# fpga13-serdes-power.net
KiCad netlist of a schematic drawn in Altium Designer
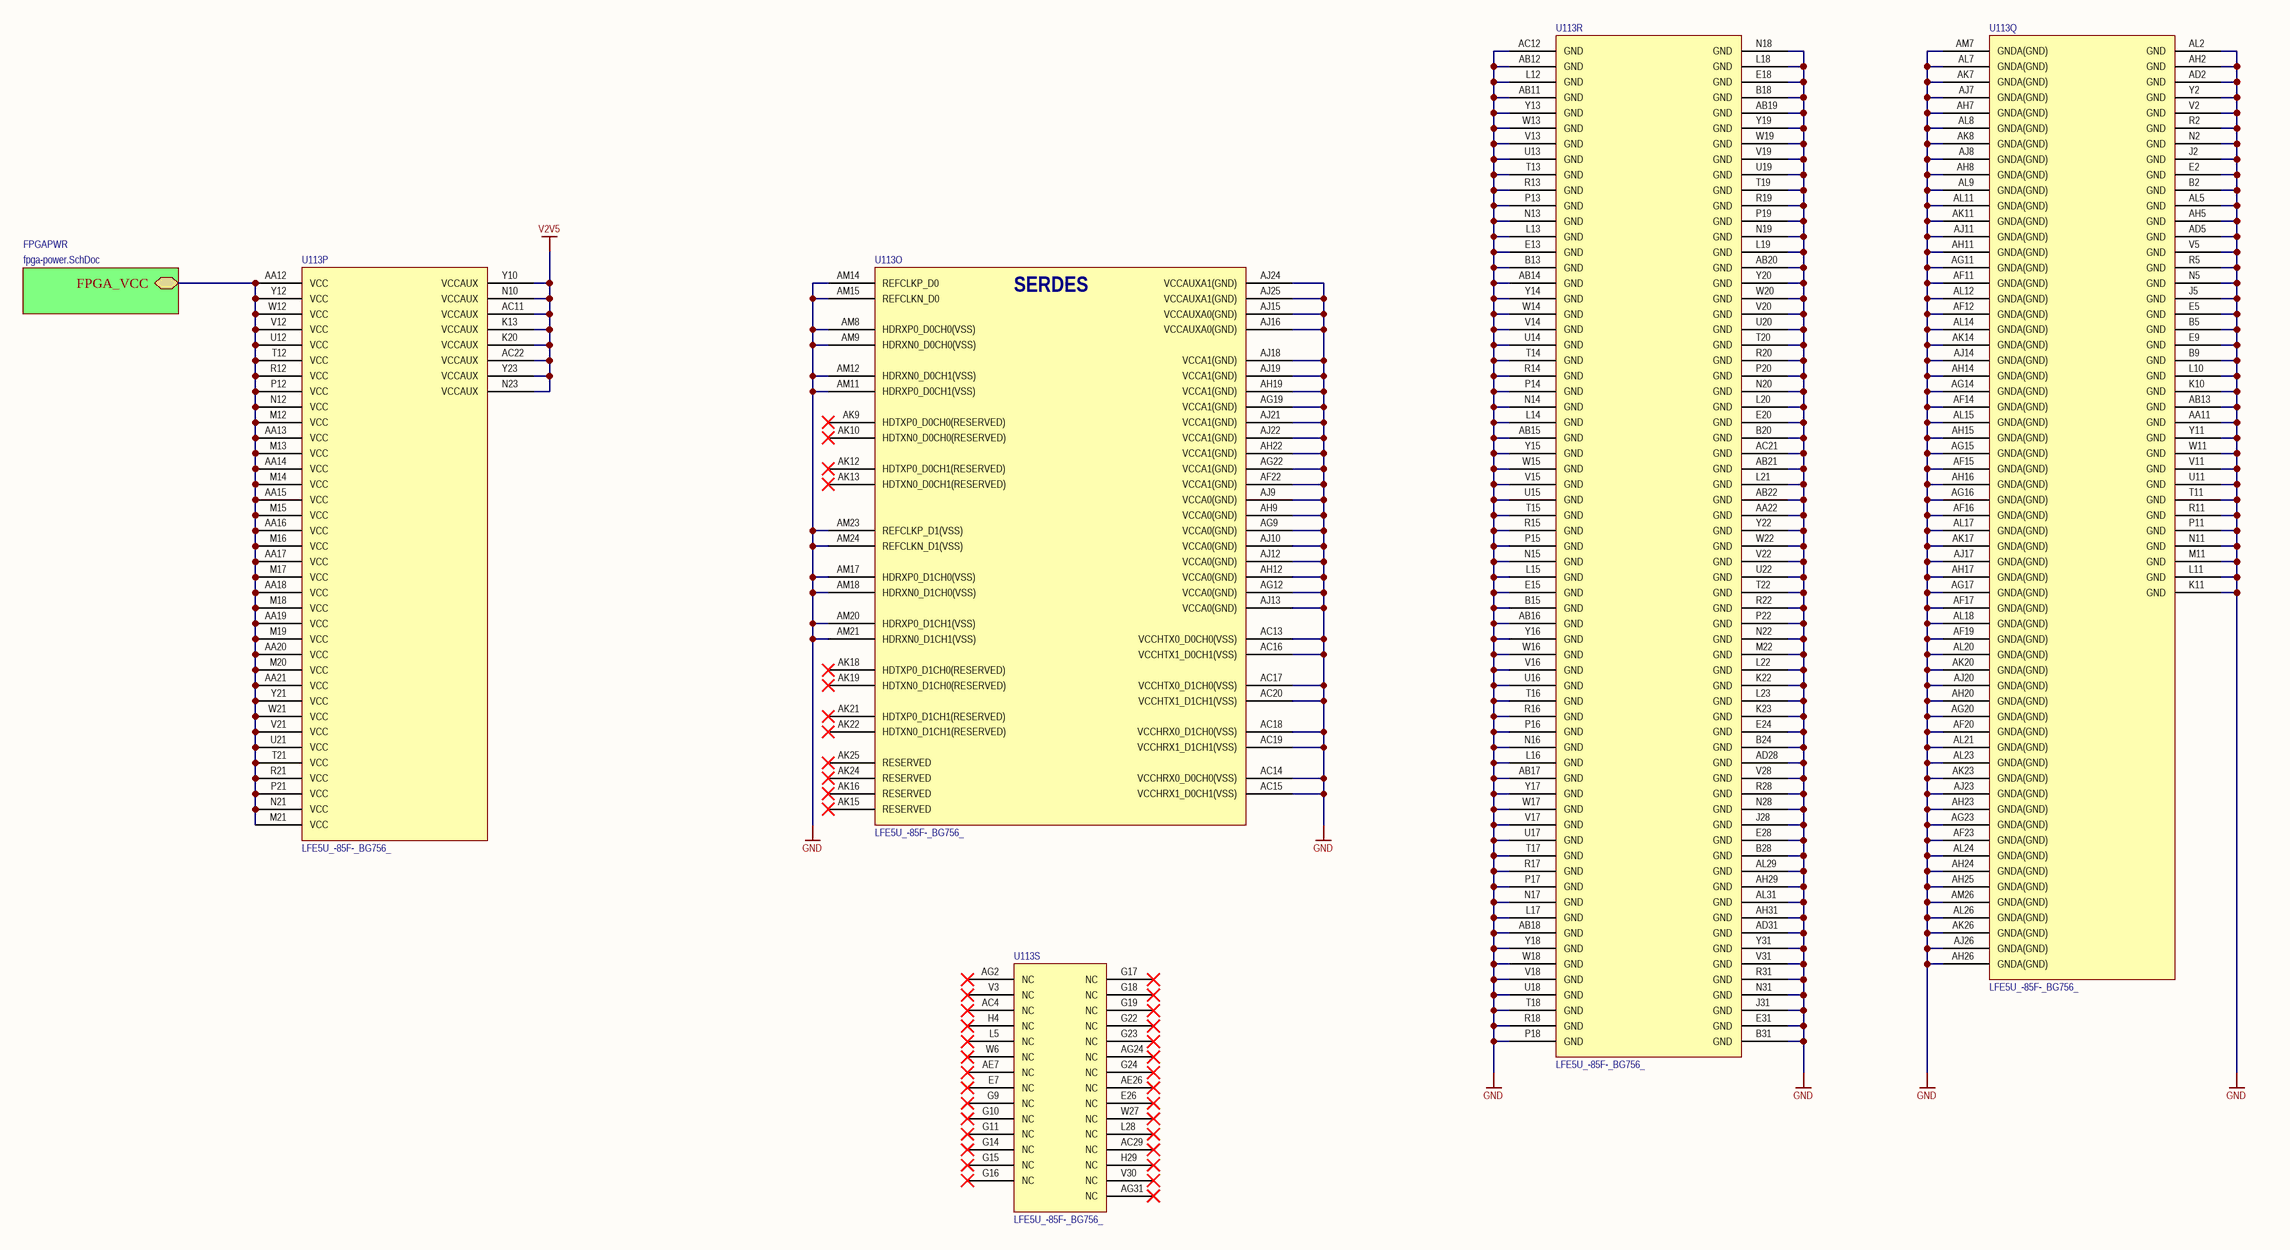
[diagram p0: fpga13-serdes-power.SchDoc]

(export (version "E")
  (design (tool "Eeschema 10.0.6"))
  (components
    (comp (ref "U113")
      (value "LFE5U_-85F-_BG756_")
      (footprint "lattice:caBGA756")
      (description "ECP5 FPGA, 85k LUT, 756-caBGA")
      (fields (field (name "MANUFACTURER") "Lattice Semiconductor"))
      (libsource (lib "lattice") (part "LFE5U_-85F-_BG756_"))
    )
  )
  (nets
    (net (code "1") (name "/FPGA_VCC") (class "Default")
      (node (ref "U113") (pin "AA12") (pinfunction "VCC_AA12") (pintype "power_in"))
      (node (ref "U113") (pin "AA13") (pinfunction "VCC_AA13") (pintype "power_in"))
      (node (ref "U113") (pin "AA14") (pinfunction "VCC_AA14") (pintype "power_in"))
      (node (ref "U113") (pin "AA15") (pinfunction "VCC_AA15") (pintype "power_in"))
      (node (ref "U113") (pin "AA16") (pinfunction "VCC_AA16") (pintype "power_in"))
      (node (ref "U113") (pin "AA17") (pinfunction "VCC_AA17") (pintype "power_in"))
      (node (ref "U113") (pin "AA18") (pinfunction "VCC_AA18") (pintype "power_in"))
      (node (ref "U113") (pin "AA19") (pinfunction "VCC_AA19") (pintype "power_in"))
      (node (ref "U113") (pin "AA20") (pinfunction "VCC_AA20") (pintype "power_in"))
      (node (ref "U113") (pin "AA21") (pinfunction "VCC_AA21") (pintype "power_in"))
      (node (ref "U113") (pin "M12") (pinfunction "VCC_M12") (pintype "power_in"))
      (node (ref "U113") (pin "M13") (pinfunction "VCC_M13") (pintype "power_in"))
      (node (ref "U113") (pin "M14") (pinfunction "VCC_M14") (pintype "power_in"))
      (node (ref "U113") (pin "M15") (pinfunction "VCC_M15") (pintype "power_in"))
      (node (ref "U113") (pin "M16") (pinfunction "VCC_M16") (pintype "power_in"))
      (node (ref "U113") (pin "M17") (pinfunction "VCC_M17") (pintype "power_in"))
      (node (ref "U113") (pin "M18") (pinfunction "VCC_M18") (pintype "power_in"))
      (node (ref "U113") (pin "M19") (pinfunction "VCC_M19") (pintype "power_in"))
      (node (ref "U113") (pin "M20") (pinfunction "VCC_M20") (pintype "power_in"))
      (node (ref "U113") (pin "M21") (pinfunction "VCC_M21") (pintype "power_in"))
      (node (ref "U113") (pin "N12") (pinfunction "VCC_N12") (pintype "power_in"))
      (node (ref "U113") (pin "N21") (pinfunction "VCC_N21") (pintype "power_in"))
      (node (ref "U113") (pin "P12") (pinfunction "VCC_P12") (pintype "power_in"))
      (node (ref "U113") (pin "P21") (pinfunction "VCC_P21") (pintype "power_in"))
      (node (ref "U113") (pin "R12") (pinfunction "VCC_R12") (pintype "power_in"))
      (node (ref "U113") (pin "R21") (pinfunction "VCC_R21") (pintype "power_in"))
      (node (ref "U113") (pin "T12") (pinfunction "VCC_T12") (pintype "power_in"))
      (node (ref "U113") (pin "T21") (pinfunction "VCC_T21") (pintype "power_in"))
      (node (ref "U113") (pin "U12") (pinfunction "VCC_U12") (pintype "power_in"))
      (node (ref "U113") (pin "U21") (pinfunction "VCC_U21") (pintype "power_in"))
      (node (ref "U113") (pin "V12") (pinfunction "VCC_V12") (pintype "power_in"))
      (node (ref "U113") (pin "V21") (pinfunction "VCC_V21") (pintype "power_in"))
      (node (ref "U113") (pin "W12") (pinfunction "VCC_W12") (pintype "power_in"))
      (node (ref "U113") (pin "W21") (pinfunction "VCC_W21") (pintype "power_in"))
      (node (ref "U113") (pin "Y12") (pinfunction "VCC_Y12") (pintype "power_in"))
      (node (ref "U113") (pin "Y21") (pinfunction "VCC_Y21") (pintype "power_in"))
    )
    (net (code "2") (name "GND") (class "Default")
      (node (ref "U113") (pin "AA11") (pinfunction "GND_AA11") (pintype "power_in"))
      (node (ref "U113") (pin "AA22") (pinfunction "GND_AA22") (pintype "power_in"))
      (node (ref "U113") (pin "AB11") (pinfunction "GND_AB11") (pintype "power_in"))
      (node (ref "U113") (pin "AB12") (pinfunction "GND_AB12") (pintype "power_in"))
      (node (ref "U113") (pin "AB13") (pinfunction "GND_AB13") (pintype "power_in"))
      (node (ref "U113") (pin "AB14") (pinfunction "GND_AB14") (pintype "power_in"))
      (node (ref "U113") (pin "AB15") (pinfunction "GND_AB15") (pintype "power_in"))
      (node (ref "U113") (pin "AB16") (pinfunction "GND_AB16") (pintype "power_in"))
      (node (ref "U113") (pin "AB17") (pinfunction "GND_AB17") (pintype "power_in"))
      (node (ref "U113") (pin "AB18") (pinfunction "GND_AB18") (pintype "power_in"))
      (node (ref "U113") (pin "AB19") (pinfunction "GND_AB19") (pintype "power_in"))
      (node (ref "U113") (pin "AB20") (pinfunction "GND_AB20") (pintype "power_in"))
      (node (ref "U113") (pin "AB21") (pinfunction "GND_AB21") (pintype "power_in"))
      (node (ref "U113") (pin "AB22") (pinfunction "GND_AB22") (pintype "power_in"))
      (node (ref "U113") (pin "AC12") (pinfunction "GND_AC12") (pintype "power_in"))
      (node (ref "U113") (pin "AC13") (pinfunction "VCCHTX0_D0CH0(VSS)_AC13") (pintype "power_in"))
      (node (ref "U113") (pin "AC14") (pinfunction "VCCHRX0_D0CH0(VSS)_AC14") (pintype "power_in"))
      (node (ref "U113") (pin "AC15") (pinfunction "VCCHRX1_D0CH1(VSS)_AC15") (pintype "power_in"))
      (node (ref "U113") (pin "AC16") (pinfunction "VCCHTX1_D0CH1(VSS)_AC16") (pintype "power_in"))
      (node (ref "U113") (pin "AC17") (pinfunction "VCCHTX0_D1CH0(VSS)_AC17") (pintype "power_in"))
      (node (ref "U113") (pin "AC18") (pinfunction "VCCHRX0_D1CH0(VSS)_AC18") (pintype "power_in"))
      (node (ref "U113") (pin "AC19") (pinfunction "VCCHRX1_D1CH1(VSS)_AC19") (pintype "power_in"))
      (node (ref "U113") (pin "AC20") (pinfunction "VCCHTX1_D1CH1(VSS)_AC20") (pintype "power_in"))
      (node (ref "U113") (pin "AC21") (pinfunction "GND_AC21") (pintype "power_in"))
      (node (ref "U113") (pin "AD2") (pinfunction "GND_AD2") (pintype "power_in"))
      (node (ref "U113") (pin "AD28") (pinfunction "GND_AD28") (pintype "power_in"))
      (node (ref "U113") (pin "AD31") (pinfunction "GND_AD31") (pintype "power_in"))
      (node (ref "U113") (pin "AD5") (pinfunction "GND_AD5") (pintype "power_in"))
      (node (ref "U113") (pin "AF11") (pinfunction "GNDA(GND)_AF11") (pintype "power_in"))
      (node (ref "U113") (pin "AF12") (pinfunction "GNDA(GND)_AF12") (pintype "power_in"))
      (node (ref "U113") (pin "AF14") (pinfunction "GNDA(GND)_AF14") (pintype "power_in"))
      (node (ref "U113") (pin "AF15") (pinfunction "GNDA(GND)_AF15") (pintype "power_in"))
      (node (ref "U113") (pin "AF16") (pinfunction "GNDA(GND)_AF16") (pintype "power_in"))
      (node (ref "U113") (pin "AF17") (pinfunction "GNDA(GND)_AF17") (pintype "power_in"))
      (node (ref "U113") (pin "AF19") (pinfunction "GNDA(GND)_AF19") (pintype "power_in"))
      (node (ref "U113") (pin "AF20") (pinfunction "GNDA(GND)_AF20") (pintype "power_in"))
      (node (ref "U113") (pin "AF22") (pinfunction "VCCA1(GND)_AF22") (pintype "power_in"))
      (node (ref "U113") (pin "AF23") (pinfunction "GNDA(GND)_AF23") (pintype "power_in"))
      (node (ref "U113") (pin "AG11") (pinfunction "GNDA(GND)_AG11") (pintype "power_in"))
      (node (ref "U113") (pin "AG12") (pinfunction "VCCA0(GND)_AG12") (pintype "power_in"))
      (node (ref "U113") (pin "AG14") (pinfunction "GNDA(GND)_AG14") (pintype "power_in"))
      (node (ref "U113") (pin "AG15") (pinfunction "GNDA(GND)_AG15") (pintype "power_in"))
      (node (ref "U113") (pin "AG16") (pinfunction "GNDA(GND)_AG16") (pintype "power_in"))
      (node (ref "U113") (pin "AG17") (pinfunction "GNDA(GND)_AG17") (pintype "power_in"))
      (node (ref "U113") (pin "AG19") (pinfunction "VCCA1(GND)_AG19") (pintype "power_in"))
      (node (ref "U113") (pin "AG20") (pinfunction "GNDA(GND)_AG20") (pintype "power_in"))
      (node (ref "U113") (pin "AG22") (pinfunction "VCCA1(GND)_AG22") (pintype "power_in"))
      (node (ref "U113") (pin "AG23") (pinfunction "GNDA(GND)_AG23") (pintype "power_in"))
      (node (ref "U113") (pin "AG9") (pinfunction "VCCA0(GND)_AG9") (pintype "power_in"))
      (node (ref "U113") (pin "AH11") (pinfunction "GNDA(GND)_AH11") (pintype "power_in"))
      (node (ref "U113") (pin "AH12") (pinfunction "VCCA0(GND)_AH12") (pintype "power_in"))
      (node (ref "U113") (pin "AH14") (pinfunction "GNDA(GND)_AH14") (pintype "power_in"))
      (node (ref "U113") (pin "AH15") (pinfunction "GNDA(GND)_AH15") (pintype "power_in"))
      (node (ref "U113") (pin "AH16") (pinfunction "GNDA(GND)_AH16") (pintype "power_in"))
      (node (ref "U113") (pin "AH17") (pinfunction "GNDA(GND)_AH17") (pintype "power_in"))
      (node (ref "U113") (pin "AH19") (pinfunction "VCCA1(GND)_AH19") (pintype "power_in"))
      (node (ref "U113") (pin "AH2") (pinfunction "GND_AH2") (pintype "power_in"))
      (node (ref "U113") (pin "AH20") (pinfunction "GNDA(GND)_AH20") (pintype "power_in"))
      (node (ref "U113") (pin "AH22") (pinfunction "VCCA1(GND)_AH22") (pintype "power_in"))
      (node (ref "U113") (pin "AH23") (pinfunction "GNDA(GND)_AH23") (pintype "power_in"))
      (node (ref "U113") (pin "AH24") (pinfunction "GNDA(GND)_AH24") (pintype "power_in"))
      (node (ref "U113") (pin "AH25") (pinfunction "GNDA(GND)_AH25") (pintype "power_in"))
      (node (ref "U113") (pin "AH26") (pinfunction "GNDA(GND)_AH26") (pintype "power_in"))
      (node (ref "U113") (pin "AH29") (pinfunction "GND_AH29") (pintype "power_in"))
      (node (ref "U113") (pin "AH31") (pinfunction "GND_AH31") (pintype "power_in"))
      (node (ref "U113") (pin "AH5") (pinfunction "GND_AH5") (pintype "power_in"))
      (node (ref "U113") (pin "AH7") (pinfunction "GNDA(GND)_AH7") (pintype "power_in"))
      (node (ref "U113") (pin "AH8") (pinfunction "GNDA(GND)_AH8") (pintype "power_in"))
      (node (ref "U113") (pin "AH9") (pinfunction "VCCA0(GND)_AH9") (pintype "power_in"))
      (node (ref "U113") (pin "AJ10") (pinfunction "VCCA0(GND)_AJ10") (pintype "power_in"))
      (node (ref "U113") (pin "AJ11") (pinfunction "GNDA(GND)_AJ11") (pintype "power_in"))
      (node (ref "U113") (pin "AJ12") (pinfunction "VCCA0(GND)_AJ12") (pintype "power_in"))
      (node (ref "U113") (pin "AJ13") (pinfunction "VCCA0(GND)_AJ13") (pintype "power_in"))
      (node (ref "U113") (pin "AJ14") (pinfunction "GNDA(GND)_AJ14") (pintype "power_in"))
      (node (ref "U113") (pin "AJ15") (pinfunction "VCCAUXA0(GND)_AJ15") (pintype "power_in"))
      (node (ref "U113") (pin "AJ16") (pinfunction "VCCAUXA0(GND)_AJ16") (pintype "power_in"))
      (node (ref "U113") (pin "AJ17") (pinfunction "GNDA(GND)_AJ17") (pintype "power_in"))
      (node (ref "U113") (pin "AJ18") (pinfunction "VCCA1(GND)_AJ18") (pintype "power_in"))
      (node (ref "U113") (pin "AJ19") (pinfunction "VCCA1(GND)_AJ19") (pintype "power_in"))
      (node (ref "U113") (pin "AJ20") (pinfunction "GNDA(GND)_AJ20") (pintype "power_in"))
      (node (ref "U113") (pin "AJ21") (pinfunction "VCCA1(GND)_AJ21") (pintype "power_in"))
      (node (ref "U113") (pin "AJ22") (pinfunction "VCCA1(GND)_AJ22") (pintype "power_in"))
      (node (ref "U113") (pin "AJ23") (pinfunction "GNDA(GND)_AJ23") (pintype "power_in"))
      (node (ref "U113") (pin "AJ24") (pinfunction "VCCAUXA1(GND)_AJ24") (pintype "power_in"))
      (node (ref "U113") (pin "AJ25") (pinfunction "VCCAUXA1(GND)_AJ25") (pintype "power_in"))
      (node (ref "U113") (pin "AJ26") (pinfunction "GNDA(GND)_AJ26") (pintype "power_in"))
      (node (ref "U113") (pin "AJ7") (pinfunction "GNDA(GND)_AJ7") (pintype "power_in"))
      (node (ref "U113") (pin "AJ8") (pinfunction "GNDA(GND)_AJ8") (pintype "power_in"))
      (node (ref "U113") (pin "AJ9") (pinfunction "VCCA0(GND)_AJ9") (pintype "power_in"))
      (node (ref "U113") (pin "AK11") (pinfunction "GNDA(GND)_AK11") (pintype "power_in"))
      (node (ref "U113") (pin "AK14") (pinfunction "GNDA(GND)_AK14") (pintype "power_in"))
      (node (ref "U113") (pin "AK17") (pinfunction "GNDA(GND)_AK17") (pintype "power_in"))
      (node (ref "U113") (pin "AK20") (pinfunction "GNDA(GND)_AK20") (pintype "power_in"))
      (node (ref "U113") (pin "AK23") (pinfunction "GNDA(GND)_AK23") (pintype "power_in"))
      (node (ref "U113") (pin "AK26") (pinfunction "GNDA(GND)_AK26") (pintype "power_in"))
      (node (ref "U113") (pin "AK7") (pinfunction "GNDA(GND)_AK7") (pintype "power_in"))
      (node (ref "U113") (pin "AK8") (pinfunction "GNDA(GND)_AK8") (pintype "power_in"))
      (node (ref "U113") (pin "AL11") (pinfunction "GNDA(GND)_AL11") (pintype "power_in"))
      (node (ref "U113") (pin "AL12") (pinfunction "GNDA(GND)_AL12") (pintype "power_in"))
      (node (ref "U113") (pin "AL14") (pinfunction "GNDA(GND)_AL14") (pintype "power_in"))
      (node (ref "U113") (pin "AL15") (pinfunction "GNDA(GND)_AL15") (pintype "power_in"))
      (node (ref "U113") (pin "AL17") (pinfunction "GNDA(GND)_AL17") (pintype "power_in"))
      (node (ref "U113") (pin "AL18") (pinfunction "GNDA(GND)_AL18") (pintype "power_in"))
      (node (ref "U113") (pin "AL2") (pinfunction "GND_AL2") (pintype "power_in"))
      (node (ref "U113") (pin "AL20") (pinfunction "GNDA(GND)_AL20") (pintype "power_in"))
      (node (ref "U113") (pin "AL21") (pinfunction "GNDA(GND)_AL21") (pintype "power_in"))
      (node (ref "U113") (pin "AL23") (pinfunction "GNDA(GND)_AL23") (pintype "power_in"))
      (node (ref "U113") (pin "AL24") (pinfunction "GNDA(GND)_AL24") (pintype "power_in"))
      (node (ref "U113") (pin "AL26") (pinfunction "GNDA(GND)_AL26") (pintype "power_in"))
      (node (ref "U113") (pin "AL29") (pinfunction "GND_AL29") (pintype "power_in"))
      (node (ref "U113") (pin "AL31") (pinfunction "GND_AL31") (pintype "power_in"))
      (node (ref "U113") (pin "AL5") (pinfunction "GND_AL5") (pintype "power_in"))
      (node (ref "U113") (pin "AL7") (pinfunction "GNDA(GND)_AL7") (pintype "power_in"))
      (node (ref "U113") (pin "AL8") (pinfunction "GNDA(GND)_AL8") (pintype "power_in"))
      (node (ref "U113") (pin "AL9") (pinfunction "GNDA(GND)_AL9") (pintype "power_in"))
      (node (ref "U113") (pin "AM11") (pinfunction "HDRXP0_D0CH1(VSS)_AM11") (pintype "passive"))
      (node (ref "U113") (pin "AM12") (pinfunction "HDRXN0_D0CH1(VSS)_AM12") (pintype "passive"))
      (node (ref "U113") (pin "AM14") (pinfunction "REFCLKP_D0_AM14") (pintype "passive"))
      (node (ref "U113") (pin "AM15") (pinfunction "REFCLKN_D0_AM15") (pintype "passive"))
      (node (ref "U113") (pin "AM17") (pinfunction "HDRXP0_D1CH0(VSS)_AM17") (pintype "passive"))
      (node (ref "U113") (pin "AM18") (pinfunction "HDRXN0_D1CH0(VSS)_AM18") (pintype "passive"))
      (node (ref "U113") (pin "AM20") (pinfunction "HDRXP0_D1CH1(VSS)_AM20") (pintype "passive"))
      (node (ref "U113") (pin "AM21") (pinfunction "HDRXN0_D1CH1(VSS)_AM21") (pintype "passive"))
      (node (ref "U113") (pin "AM23") (pinfunction "REFCLKP_D1(VSS)_AM23") (pintype "passive"))
      (node (ref "U113") (pin "AM24") (pinfunction "REFCLKN_D1(VSS)_AM24") (pintype "passive"))
      (node (ref "U113") (pin "AM26") (pinfunction "GNDA(GND)_AM26") (pintype "power_in"))
      (node (ref "U113") (pin "AM7") (pinfunction "GNDA(GND)_AM7") (pintype "power_in"))
      (node (ref "U113") (pin "AM8") (pinfunction "HDRXP0_D0CH0(VSS)_AM8") (pintype "passive"))
      (node (ref "U113") (pin "AM9") (pinfunction "HDRXN0_D0CH0(VSS)_AM9") (pintype "passive"))
      (node (ref "U113") (pin "B13") (pinfunction "GND_B13") (pintype "power_in"))
      (node (ref "U113") (pin "B15") (pinfunction "GND_B15") (pintype "power_in"))
      (node (ref "U113") (pin "B18") (pinfunction "GND_B18") (pintype "power_in"))
      (node (ref "U113") (pin "B2") (pinfunction "GND_B2") (pintype "power_in"))
      (node (ref "U113") (pin "B20") (pinfunction "GND_B20") (pintype "power_in"))
      (node (ref "U113") (pin "B24") (pinfunction "GND_B24") (pintype "power_in"))
      (node (ref "U113") (pin "B28") (pinfunction "GND_B28") (pintype "power_in"))
      (node (ref "U113") (pin "B31") (pinfunction "GND_B31") (pintype "power_in"))
      (node (ref "U113") (pin "B5") (pinfunction "GND_B5") (pintype "power_in"))
      (node (ref "U113") (pin "B9") (pinfunction "GND_B9") (pintype "power_in"))
      (node (ref "U113") (pin "E13") (pinfunction "GND_E13") (pintype "power_in"))
      (node (ref "U113") (pin "E15") (pinfunction "GND_E15") (pintype "power_in"))
      (node (ref "U113") (pin "E18") (pinfunction "GND_E18") (pintype "power_in"))
      (node (ref "U113") (pin "E2") (pinfunction "GND_E2") (pintype "power_in"))
      (node (ref "U113") (pin "E20") (pinfunction "GND_E20") (pintype "power_in"))
      (node (ref "U113") (pin "E24") (pinfunction "GND_E24") (pintype "power_in"))
      (node (ref "U113") (pin "E28") (pinfunction "GND_E28") (pintype "power_in"))
      (node (ref "U113") (pin "E31") (pinfunction "GND_E31") (pintype "power_in"))
      (node (ref "U113") (pin "E5") (pinfunction "GND_E5") (pintype "power_in"))
      (node (ref "U113") (pin "E9") (pinfunction "GND_E9") (pintype "power_in"))
      (node (ref "U113") (pin "J2") (pinfunction "GND_J2") (pintype "power_in"))
      (node (ref "U113") (pin "J28") (pinfunction "GND_J28") (pintype "power_in"))
      (node (ref "U113") (pin "J31") (pinfunction "GND_J31") (pintype "power_in"))
      (node (ref "U113") (pin "J5") (pinfunction "GND_J5") (pintype "power_in"))
      (node (ref "U113") (pin "K10") (pinfunction "GND_K10") (pintype "power_in"))
      (node (ref "U113") (pin "K11") (pinfunction "GND_K11") (pintype "power_in"))
      (node (ref "U113") (pin "K22") (pinfunction "GND_K22") (pintype "power_in"))
      (node (ref "U113") (pin "K23") (pinfunction "GND_K23") (pintype "power_in"))
      (node (ref "U113") (pin "L10") (pinfunction "GND_L10") (pintype "power_in"))
      (node (ref "U113") (pin "L11") (pinfunction "GND_L11") (pintype "power_in"))
      (node (ref "U113") (pin "L12") (pinfunction "GND_L12") (pintype "power_in"))
      (node (ref "U113") (pin "L13") (pinfunction "GND_L13") (pintype "power_in"))
      (node (ref "U113") (pin "L14") (pinfunction "GND_L14") (pintype "power_in"))
      (node (ref "U113") (pin "L15") (pinfunction "GND_L15") (pintype "power_in"))
      (node (ref "U113") (pin "L16") (pinfunction "GND_L16") (pintype "power_in"))
      (node (ref "U113") (pin "L17") (pinfunction "GND_L17") (pintype "power_in"))
      (node (ref "U113") (pin "L18") (pinfunction "GND_L18") (pintype "power_in"))
      (node (ref "U113") (pin "L19") (pinfunction "GND_L19") (pintype "power_in"))
      (node (ref "U113") (pin "L20") (pinfunction "GND_L20") (pintype "power_in"))
      (node (ref "U113") (pin "L21") (pinfunction "GND_L21") (pintype "power_in"))
      (node (ref "U113") (pin "L22") (pinfunction "GND_L22") (pintype "power_in"))
      (node (ref "U113") (pin "L23") (pinfunction "GND_L23") (pintype "power_in"))
      (node (ref "U113") (pin "M11") (pinfunction "GND_M11") (pintype "power_in"))
      (node (ref "U113") (pin "M22") (pinfunction "GND_M22") (pintype "power_in"))
      (node (ref "U113") (pin "N11") (pinfunction "GND_N11") (pintype "power_in"))
      (node (ref "U113") (pin "N13") (pinfunction "GND_N13") (pintype "power_in"))
      (node (ref "U113") (pin "N14") (pinfunction "GND_N14") (pintype "power_in"))
      (node (ref "U113") (pin "N15") (pinfunction "GND_N15") (pintype "power_in"))
      (node (ref "U113") (pin "N16") (pinfunction "GND_N16") (pintype "power_in"))
      (node (ref "U113") (pin "N17") (pinfunction "GND_N17") (pintype "power_in"))
      (node (ref "U113") (pin "N18") (pinfunction "GND_N18") (pintype "power_in"))
      (node (ref "U113") (pin "N19") (pinfunction "GND_N19") (pintype "power_in"))
      (node (ref "U113") (pin "N2") (pinfunction "GND_N2") (pintype "power_in"))
      (node (ref "U113") (pin "N20") (pinfunction "GND_N20") (pintype "power_in"))
      (node (ref "U113") (pin "N22") (pinfunction "GND_N22") (pintype "power_in"))
      (node (ref "U113") (pin "N28") (pinfunction "GND_N28") (pintype "power_in"))
      (node (ref "U113") (pin "N31") (pinfunction "GND_N31") (pintype "power_in"))
      (node (ref "U113") (pin "N5") (pinfunction "GND_N5") (pintype "power_in"))
      (node (ref "U113") (pin "P11") (pinfunction "GND_P11") (pintype "power_in"))
      (node (ref "U113") (pin "P13") (pinfunction "GND_P13") (pintype "power_in"))
      (node (ref "U113") (pin "P14") (pinfunction "GND_P14") (pintype "power_in"))
      (node (ref "U113") (pin "P15") (pinfunction "GND_P15") (pintype "power_in"))
      (node (ref "U113") (pin "P16") (pinfunction "GND_P16") (pintype "power_in"))
      (node (ref "U113") (pin "P17") (pinfunction "GND_P17") (pintype "power_in"))
      (node (ref "U113") (pin "P18") (pinfunction "GND_P18") (pintype "power_in"))
      (node (ref "U113") (pin "P19") (pinfunction "GND_P19") (pintype "power_in"))
      (node (ref "U113") (pin "P20") (pinfunction "GND_P20") (pintype "power_in"))
      (node (ref "U113") (pin "P22") (pinfunction "GND_P22") (pintype "power_in"))
      (node (ref "U113") (pin "R11") (pinfunction "GND_R11") (pintype "power_in"))
      (node (ref "U113") (pin "R13") (pinfunction "GND_R13") (pintype "power_in"))
      (node (ref "U113") (pin "R14") (pinfunction "GND_R14") (pintype "power_in"))
      (node (ref "U113") (pin "R15") (pinfunction "GND_R15") (pintype "power_in"))
      (node (ref "U113") (pin "R16") (pinfunction "GND_R16") (pintype "power_in"))
      (node (ref "U113") (pin "R17") (pinfunction "GND_R17") (pintype "power_in"))
      (node (ref "U113") (pin "R18") (pinfunction "GND_R18") (pintype "power_in"))
      (node (ref "U113") (pin "R19") (pinfunction "GND_R19") (pintype "power_in"))
      (node (ref "U113") (pin "R2") (pinfunction "GND_R2") (pintype "power_in"))
      (node (ref "U113") (pin "R20") (pinfunction "GND_R20") (pintype "power_in"))
      (node (ref "U113") (pin "R22") (pinfunction "GND_R22") (pintype "power_in"))
      (node (ref "U113") (pin "R28") (pinfunction "GND_R28") (pintype "power_in"))
      (node (ref "U113") (pin "R31") (pinfunction "GND_R31") (pintype "power_in"))
      (node (ref "U113") (pin "R5") (pinfunction "GND_R5") (pintype "power_in"))
      (node (ref "U113") (pin "T11") (pinfunction "GND_T11") (pintype "power_in"))
      (node (ref "U113") (pin "T13") (pinfunction "GND_T13") (pintype "power_in"))
      (node (ref "U113") (pin "T14") (pinfunction "GND_T14") (pintype "power_in"))
      (node (ref "U113") (pin "T15") (pinfunction "GND_T15") (pintype "power_in"))
      (node (ref "U113") (pin "T16") (pinfunction "GND_T16") (pintype "power_in"))
      (node (ref "U113") (pin "T17") (pinfunction "GND_T17") (pintype "power_in"))
      (node (ref "U113") (pin "T18") (pinfunction "GND_T18") (pintype "power_in"))
      (node (ref "U113") (pin "T19") (pinfunction "GND_T19") (pintype "power_in"))
      (node (ref "U113") (pin "T20") (pinfunction "GND_T20") (pintype "power_in"))
      (node (ref "U113") (pin "T22") (pinfunction "GND_T22") (pintype "power_in"))
      (node (ref "U113") (pin "U11") (pinfunction "GND_U11") (pintype "power_in"))
      (node (ref "U113") (pin "U13") (pinfunction "GND_U13") (pintype "power_in"))
      (node (ref "U113") (pin "U14") (pinfunction "GND_U14") (pintype "power_in"))
      (node (ref "U113") (pin "U15") (pinfunction "GND_U15") (pintype "power_in"))
      (node (ref "U113") (pin "U16") (pinfunction "GND_U16") (pintype "power_in"))
      (node (ref "U113") (pin "U17") (pinfunction "GND_U17") (pintype "power_in"))
      (node (ref "U113") (pin "U18") (pinfunction "GND_U18") (pintype "power_in"))
      (node (ref "U113") (pin "U19") (pinfunction "GND_U19") (pintype "power_in"))
      (node (ref "U113") (pin "U20") (pinfunction "GND_U20") (pintype "power_in"))
      (node (ref "U113") (pin "U22") (pinfunction "GND_U22") (pintype "power_in"))
      (node (ref "U113") (pin "V11") (pinfunction "GND_V11") (pintype "power_in"))
      (node (ref "U113") (pin "V13") (pinfunction "GND_V13") (pintype "power_in"))
      (node (ref "U113") (pin "V14") (pinfunction "GND_V14") (pintype "power_in"))
      (node (ref "U113") (pin "V15") (pinfunction "GND_V15") (pintype "power_in"))
      (node (ref "U113") (pin "V16") (pinfunction "GND_V16") (pintype "power_in"))
      (node (ref "U113") (pin "V17") (pinfunction "GND_V17") (pintype "power_in"))
      (node (ref "U113") (pin "V18") (pinfunction "GND_V18") (pintype "power_in"))
      (node (ref "U113") (pin "V19") (pinfunction "GND_V19") (pintype "power_in"))
      (node (ref "U113") (pin "V2") (pinfunction "GND_V2") (pintype "power_in"))
      (node (ref "U113") (pin "V20") (pinfunction "GND_V20") (pintype "power_in"))
      (node (ref "U113") (pin "V22") (pinfunction "GND_V22") (pintype "power_in"))
      (node (ref "U113") (pin "V28") (pinfunction "GND_V28") (pintype "power_in"))
      (node (ref "U113") (pin "V31") (pinfunction "GND_V31") (pintype "power_in"))
      (node (ref "U113") (pin "V5") (pinfunction "GND_V5") (pintype "power_in"))
      (node (ref "U113") (pin "W11") (pinfunction "GND_W11") (pintype "power_in"))
      (node (ref "U113") (pin "W13") (pinfunction "GND_W13") (pintype "power_in"))
      (node (ref "U113") (pin "W14") (pinfunction "GND_W14") (pintype "power_in"))
      (node (ref "U113") (pin "W15") (pinfunction "GND_W15") (pintype "power_in"))
      (node (ref "U113") (pin "W16") (pinfunction "GND_W16") (pintype "power_in"))
      (node (ref "U113") (pin "W17") (pinfunction "GND_W17") (pintype "power_in"))
      (node (ref "U113") (pin "W18") (pinfunction "GND_W18") (pintype "power_in"))
      (node (ref "U113") (pin "W19") (pinfunction "GND_W19") (pintype "power_in"))
      (node (ref "U113") (pin "W20") (pinfunction "GND_W20") (pintype "power_in"))
      (node (ref "U113") (pin "W22") (pinfunction "GND_W22") (pintype "power_in"))
      (node (ref "U113") (pin "Y11") (pinfunction "GND_Y11") (pintype "power_in"))
      (node (ref "U113") (pin "Y13") (pinfunction "GND_Y13") (pintype "power_in"))
      (node (ref "U113") (pin "Y14") (pinfunction "GND_Y14") (pintype "power_in"))
      (node (ref "U113") (pin "Y15") (pinfunction "GND_Y15") (pintype "power_in"))
      (node (ref "U113") (pin "Y16") (pinfunction "GND_Y16") (pintype "power_in"))
      (node (ref "U113") (pin "Y17") (pinfunction "GND_Y17") (pintype "power_in"))
      (node (ref "U113") (pin "Y18") (pinfunction "GND_Y18") (pintype "power_in"))
      (node (ref "U113") (pin "Y19") (pinfunction "GND_Y19") (pintype "power_in"))
      (node (ref "U113") (pin "Y2") (pinfunction "GND_Y2") (pintype "power_in"))
      (node (ref "U113") (pin "Y20") (pinfunction "GND_Y20") (pintype "power_in"))
      (node (ref "U113") (pin "Y22") (pinfunction "GND_Y22") (pintype "power_in"))
      (node (ref "U113") (pin "Y31") (pinfunction "GND_Y31") (pintype "power_in"))
    )
    (net (code "3") (name "V2V5") (class "Default")
      (node (ref "U113") (pin "AC11") (pinfunction "VCCAUX_AC11") (pintype "power_in"))
      (node (ref "U113") (pin "AC22") (pinfunction "VCCAUX_AC22") (pintype "power_in"))
      (node (ref "U113") (pin "K13") (pinfunction "VCCAUX_K13") (pintype "power_in"))
      (node (ref "U113") (pin "K20") (pinfunction "VCCAUX_K20") (pintype "power_in"))
      (node (ref "U113") (pin "N10") (pinfunction "VCCAUX_N10") (pintype "power_in"))
      (node (ref "U113") (pin "N23") (pinfunction "VCCAUX_N23") (pintype "power_in"))
      (node (ref "U113") (pin "Y10") (pinfunction "VCCAUX_Y10") (pintype "power_in"))
      (node (ref "U113") (pin "Y23") (pinfunction "VCCAUX_Y23") (pintype "power_in"))
    )
    (net (code "4") (name "unconnected-(U113O-HDTXN0_D0CH0(RESERVED)-PadAK10)") (class "Default")
      (node (ref "U113") (pin "AK10") (pinfunction "HDTXN0_D0CH0(RESERVED)_AK10") (pintype "passive+no_connect"))
    )
    (net (code "5") (name "unconnected-(U113O-HDTXN0_D0CH1(RESERVED)-PadAK13)") (class "Default")
      (node (ref "U113") (pin "AK13") (pinfunction "HDTXN0_D0CH1(RESERVED)_AK13") (pintype "passive+no_connect"))
    )
    (net (code "6") (name "unconnected-(U113O-HDTXN0_D1CH0(RESERVED)-PadAK19)") (class "Default")
      (node (ref "U113") (pin "AK19") (pinfunction "HDTXN0_D1CH0(RESERVED)_AK19") (pintype "passive+no_connect"))
    )
    (net (code "7") (name "unconnected-(U113O-HDTXN0_D1CH1(RESERVED)-PadAK22)") (class "Default")
      (node (ref "U113") (pin "AK22") (pinfunction "HDTXN0_D1CH1(RESERVED)_AK22") (pintype "passive+no_connect"))
    )
    (net (code "8") (name "unconnected-(U113O-HDTXP0_D0CH0(RESERVED)-PadAK9)") (class "Default")
      (node (ref "U113") (pin "AK9") (pinfunction "HDTXP0_D0CH0(RESERVED)_AK9") (pintype "passive+no_connect"))
    )
    (net (code "9") (name "unconnected-(U113O-HDTXP0_D0CH1(RESERVED)-PadAK12)") (class "Default")
      (node (ref "U113") (pin "AK12") (pinfunction "HDTXP0_D0CH1(RESERVED)_AK12") (pintype "passive+no_connect"))
    )
    (net (code "10") (name "unconnected-(U113O-HDTXP0_D1CH0(RESERVED)-PadAK18)") (class "Default")
      (node (ref "U113") (pin "AK18") (pinfunction "HDTXP0_D1CH0(RESERVED)_AK18") (pintype "passive+no_connect"))
    )
    (net (code "11") (name "unconnected-(U113O-HDTXP0_D1CH1(RESERVED)-PadAK21)") (class "Default")
      (node (ref "U113") (pin "AK21") (pinfunction "HDTXP0_D1CH1(RESERVED)_AK21") (pintype "passive+no_connect"))
    )
    (net (code "12") (name "unconnected-(U113O-RESERVED-PadAK15)") (class "Default")
      (node (ref "U113") (pin "AK15") (pinfunction "RESERVED_AK15") (pintype "passive+no_connect"))
    )
    (net (code "13") (name "unconnected-(U113O-RESERVED-PadAK16)") (class "Default")
      (node (ref "U113") (pin "AK16") (pinfunction "RESERVED_AK16") (pintype "passive+no_connect"))
    )
    (net (code "14") (name "unconnected-(U113O-RESERVED-PadAK24)") (class "Default")
      (node (ref "U113") (pin "AK24") (pinfunction "RESERVED_AK24") (pintype "passive+no_connect"))
    )
    (net (code "15") (name "unconnected-(U113O-RESERVED-PadAK25)") (class "Default")
      (node (ref "U113") (pin "AK25") (pinfunction "RESERVED_AK25") (pintype "passive+no_connect"))
    )
    (net (code "16") (name "unconnected-(U113S-NC-PadAC4)") (class "Default")
      (node (ref "U113") (pin "AC4") (pinfunction "NC_AC4") (pintype "passive+no_connect"))
    )
    (net (code "17") (name "unconnected-(U113S-NC-PadAC29)") (class "Default")
      (node (ref "U113") (pin "AC29") (pinfunction "NC_AC29") (pintype "passive+no_connect"))
    )
    (net (code "18") (name "unconnected-(U113S-NC-PadAE7)") (class "Default")
      (node (ref "U113") (pin "AE7") (pinfunction "NC_AE7") (pintype "passive+no_connect"))
    )
    (net (code "19") (name "unconnected-(U113S-NC-PadAE26)") (class "Default")
      (node (ref "U113") (pin "AE26") (pinfunction "NC_AE26") (pintype "passive+no_connect"))
    )
    (net (code "20") (name "unconnected-(U113S-NC-PadAG2)") (class "Default")
      (node (ref "U113") (pin "AG2") (pinfunction "NC_AG2") (pintype "passive+no_connect"))
    )
    (net (code "21") (name "unconnected-(U113S-NC-PadAG24)") (class "Default")
      (node (ref "U113") (pin "AG24") (pinfunction "NC_AG24") (pintype "passive+no_connect"))
    )
    (net (code "22") (name "unconnected-(U113S-NC-PadAG31)") (class "Default")
      (node (ref "U113") (pin "AG31") (pinfunction "NC_AG31") (pintype "passive+no_connect"))
    )
    (net (code "23") (name "unconnected-(U113S-NC-PadE7)") (class "Default")
      (node (ref "U113") (pin "E7") (pinfunction "NC_E7") (pintype "passive+no_connect"))
    )
    (net (code "24") (name "unconnected-(U113S-NC-PadE26)") (class "Default")
      (node (ref "U113") (pin "E26") (pinfunction "NC_E26") (pintype "passive+no_connect"))
    )
    (net (code "25") (name "unconnected-(U113S-NC-PadG9)") (class "Default")
      (node (ref "U113") (pin "G9") (pinfunction "NC_G9") (pintype "passive+no_connect"))
    )
    (net (code "26") (name "unconnected-(U113S-NC-PadG10)") (class "Default")
      (node (ref "U113") (pin "G10") (pinfunction "NC_G10") (pintype "passive+no_connect"))
    )
    (net (code "27") (name "unconnected-(U113S-NC-PadG11)") (class "Default")
      (node (ref "U113") (pin "G11") (pinfunction "NC_G11") (pintype "passive+no_connect"))
    )
    (net (code "28") (name "unconnected-(U113S-NC-PadG14)") (class "Default")
      (node (ref "U113") (pin "G14") (pinfunction "NC_G14") (pintype "passive+no_connect"))
    )
    (net (code "29") (name "unconnected-(U113S-NC-PadG15)") (class "Default")
      (node (ref "U113") (pin "G15") (pinfunction "NC_G15") (pintype "passive+no_connect"))
    )
    (net (code "30") (name "unconnected-(U113S-NC-PadG16)") (class "Default")
      (node (ref "U113") (pin "G16") (pinfunction "NC_G16") (pintype "passive+no_connect"))
    )
    (net (code "31") (name "unconnected-(U113S-NC-PadG17)") (class "Default")
      (node (ref "U113") (pin "G17") (pinfunction "NC_G17") (pintype "passive+no_connect"))
    )
    (net (code "32") (name "unconnected-(U113S-NC-PadG18)") (class "Default")
      (node (ref "U113") (pin "G18") (pinfunction "NC_G18") (pintype "passive+no_connect"))
    )
    (net (code "33") (name "unconnected-(U113S-NC-PadG19)") (class "Default")
      (node (ref "U113") (pin "G19") (pinfunction "NC_G19") (pintype "passive+no_connect"))
    )
    (net (code "34") (name "unconnected-(U113S-NC-PadG22)") (class "Default")
      (node (ref "U113") (pin "G22") (pinfunction "NC_G22") (pintype "passive+no_connect"))
    )
    (net (code "35") (name "unconnected-(U113S-NC-PadG23)") (class "Default")
      (node (ref "U113") (pin "G23") (pinfunction "NC_G23") (pintype "passive+no_connect"))
    )
    (net (code "36") (name "unconnected-(U113S-NC-PadG24)") (class "Default")
      (node (ref "U113") (pin "G24") (pinfunction "NC_G24") (pintype "passive+no_connect"))
    )
    (net (code "37") (name "unconnected-(U113S-NC-PadH4)") (class "Default")
      (node (ref "U113") (pin "H4") (pinfunction "NC_H4") (pintype "passive+no_connect"))
    )
    (net (code "38") (name "unconnected-(U113S-NC-PadH29)") (class "Default")
      (node (ref "U113") (pin "H29") (pinfunction "NC_H29") (pintype "passive+no_connect"))
    )
    (net (code "39") (name "unconnected-(U113S-NC-PadL5)") (class "Default")
      (node (ref "U113") (pin "L5") (pinfunction "NC_L5") (pintype "passive+no_connect"))
    )
    (net (code "40") (name "unconnected-(U113S-NC-PadL28)") (class "Default")
      (node (ref "U113") (pin "L28") (pinfunction "NC_L28") (pintype "passive+no_connect"))
    )
    (net (code "41") (name "unconnected-(U113S-NC-PadV3)") (class "Default")
      (node (ref "U113") (pin "V3") (pinfunction "NC_V3") (pintype "passive+no_connect"))
    )
    (net (code "42") (name "unconnected-(U113S-NC-PadV30)") (class "Default")
      (node (ref "U113") (pin "V30") (pinfunction "NC_V30") (pintype "passive+no_connect"))
    )
    (net (code "43") (name "unconnected-(U113S-NC-PadW6)") (class "Default")
      (node (ref "U113") (pin "W6") (pinfunction "NC_W6") (pintype "passive+no_connect"))
    )
    (net (code "44") (name "unconnected-(U113S-NC-PadW27)") (class "Default")
      (node (ref "U113") (pin "W27") (pinfunction "NC_W27") (pintype "passive+no_connect"))
    )
  )
)
